# fuil_oil_counter.net
KiCad netlist of a schematic drawn in EAGLE
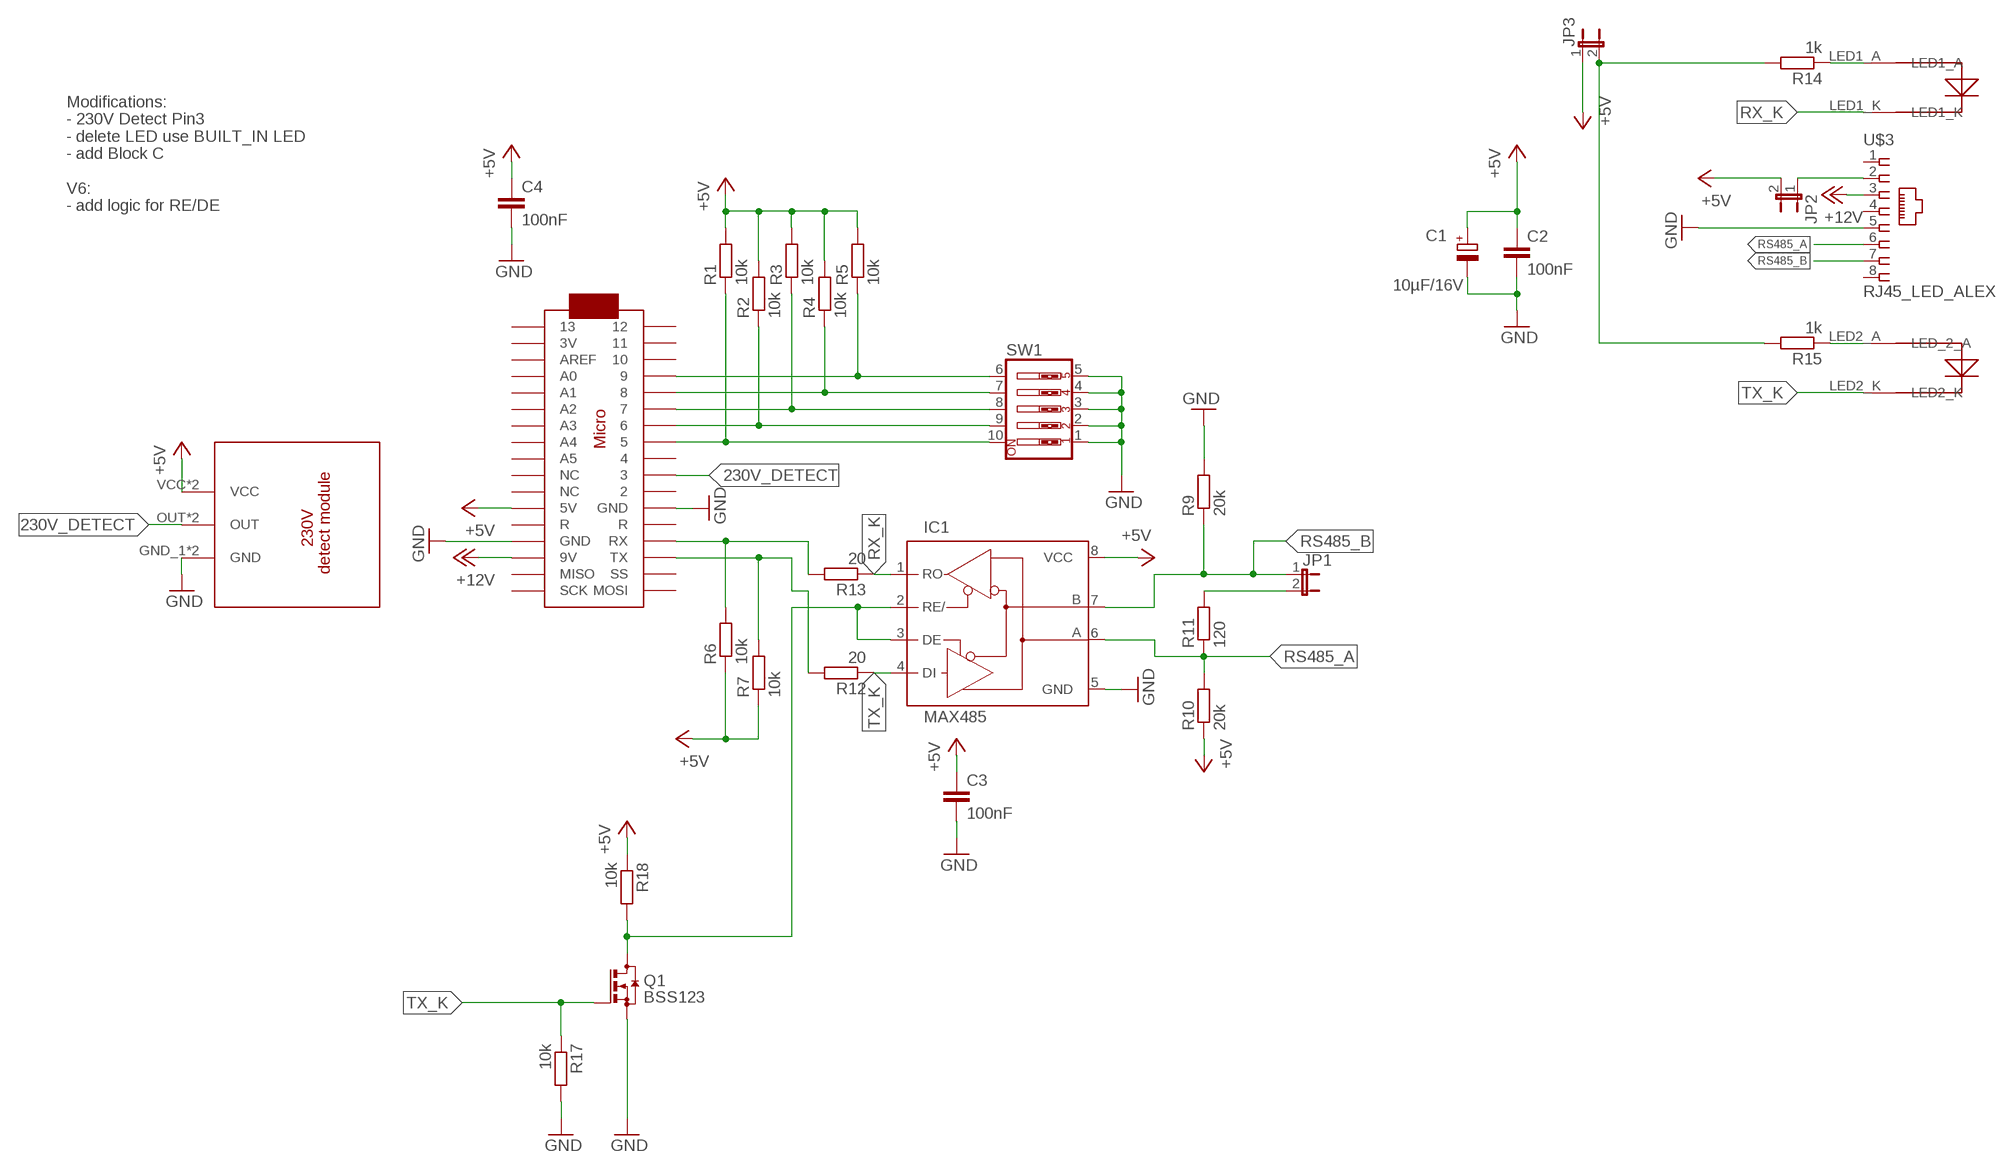
[diagram p0: schematic, sheet 1]

(export (version "E")
  (design (tool "Eeschema 10.0.6"))
  (components
    (comp (ref "C1")
      (value "10µF/16V")
      (footprint "eagle-import:SMC_C")
      (libsource (lib "eagle-import") (part "CPOL-EUSMCC"))
    )
    (comp (ref "C2")
      (value "100nF")
      (footprint "eagle-import:C0805")
      (libsource (lib "eagle-import") (part "C-EUC0805"))
    )
    (comp (ref "C3")
      (value "100nF")
      (footprint "eagle-import:C0805")
      (libsource (lib "eagle-import") (part "C-EUC0805"))
    )
    (comp (ref "C4")
      (value "100nF")
      (footprint "eagle-import:C0805")
      (libsource (lib "eagle-import") (part "C-EUC0805"))
    )
    (comp (ref "IC1")
      (value "MAX485")
      (footprint "eagle-import:SO08")
      (fields (field (name "MPN") "MAX3468ESA+T"))
      (libsource (lib "eagle-import") (part "MAX34SA68E"))
    )
    (comp (ref "JP1")
      (value "JP1E")
      (footprint "eagle-import:JP1")
      (libsource (lib "eagle-import") (part "JP1E"))
    )
    (comp (ref "JP2")
      (value "JP1E")
      (footprint "eagle-import:JP1")
      (libsource (lib "eagle-import") (part "JP1E"))
    )
    (comp (ref "JP3")
      (value "JP1E")
      (footprint "eagle-import:JP1")
      (libsource (lib "eagle-import") (part "JP1E"))
    )
    (comp (ref "Q1")
      (value "BSS123")
      (footprint "eagle-import:SOT23")
      (libsource (lib "eagle-import") (part "BSS123"))
    )
    (comp (ref "R1")
      (value "10k")
      (footprint "eagle-import:M0805")
      (libsource (lib "eagle-import") (part "R-EU_M0805"))
    )
    (comp (ref "R2")
      (value "10k")
      (footprint "eagle-import:M0805")
      (libsource (lib "eagle-import") (part "R-EU_M0805"))
    )
    (comp (ref "R3")
      (value "10k")
      (footprint "eagle-import:M0805")
      (libsource (lib "eagle-import") (part "R-EU_M0805"))
    )
    (comp (ref "R4")
      (value "10k")
      (footprint "eagle-import:M0805")
      (libsource (lib "eagle-import") (part "R-EU_M0805"))
    )
    (comp (ref "R5")
      (value "10k")
      (footprint "eagle-import:M0805")
      (libsource (lib "eagle-import") (part "R-EU_M0805"))
    )
    (comp (ref "R6")
      (value "10k")
      (footprint "eagle-import:M0805")
      (libsource (lib "eagle-import") (part "R-EU_M0805"))
    )
    (comp (ref "R7")
      (value "10k")
      (footprint "eagle-import:M0805")
      (libsource (lib "eagle-import") (part "R-EU_M0805"))
    )
    (comp (ref "R9")
      (value "20k")
      (footprint "eagle-import:M0805")
      (libsource (lib "eagle-import") (part "R-EU_M0805"))
    )
    (comp (ref "R10")
      (value "20k")
      (footprint "eagle-import:M0805")
      (libsource (lib "eagle-import") (part "R-EU_M0805"))
    )
    (comp (ref "R11")
      (value "120")
      (footprint "eagle-import:P0613_15")
      (libsource (lib "eagle-import") (part "R-EU_0613/15"))
    )
    (comp (ref "R12")
      (value "20")
      (footprint "eagle-import:M0805")
      (libsource (lib "eagle-import") (part "R-EU_M0805"))
    )
    (comp (ref "R13")
      (value "20")
      (footprint "eagle-import:M0805")
      (libsource (lib "eagle-import") (part "R-EU_M0805"))
    )
    (comp (ref "R14")
      (value "1k")
      (footprint "eagle-import:M0805")
      (libsource (lib "eagle-import") (part "R-EU_M0805"))
    )
    (comp (ref "R15")
      (value "1k")
      (footprint "eagle-import:M0805")
      (libsource (lib "eagle-import") (part "R-EU_M0805"))
    )
    (comp (ref "R17")
      (value "10k")
      (footprint "eagle-import:M0805")
      (libsource (lib "eagle-import") (part "resistor_R-EU_M0805"))
    )
    (comp (ref "R18")
      (value "10k")
      (footprint "eagle-import:M0805")
      (libsource (lib "eagle-import") (part "resistor_R-EU_M0805"))
    )
    (comp (ref "SW1")
      (value "SW_DIP-5")
      (footprint "eagle-import:EDG-05")
      (libsource (lib "eagle-import") (part "SW_DIP-5"))
    )
    (comp (ref "U$1")
      (value "ARDUINOMICRO")
      (footprint "eagle-import:ARDUINOMICRO")
      (libsource (lib "eagle-import") (part "ARDUINOMICRO"))
    )
    (comp (ref "U$2")
      (value "POWER_DETECT")
      (footprint "eagle-import:POWER_DETECT")
      (libsource (lib "eagle-import") (part "POWER_DETECT"))
    )
    (comp (ref "U$3")
      (value "RJ45_LED_ALEX")
      (footprint "eagle-import:RJ45-NO-SHIELD-WITH_LED")
      (libsource (lib "eagle-import") (part "RJ45_LED_ALEX"))
    )
  )
  (nets
    (net (code "1") (name "+5V") (class "Default")
      (node (ref "C1") (pin "+") (pinfunction "+_+") (pintype "passive"))
      (node (ref "C2") (pin "1") (pinfunction "1_1") (pintype "passive"))
      (node (ref "C3") (pin "1") (pinfunction "1_1") (pintype "passive"))
      (node (ref "C4") (pin "1") (pinfunction "1_1") (pintype "passive"))
      (node (ref "IC1") (pin "8") (pinfunction "VCC_8") (pintype "power_in"))
      (node (ref "JP2") (pin "2") (pinfunction "2_2") (pintype "passive"))
      (node (ref "JP3") (pin "1") (pinfunction "1_1") (pintype "passive"))
      (node (ref "R1") (pin "2") (pinfunction "2_2") (pintype "passive"))
      (node (ref "R10") (pin "1") (pinfunction "1_1") (pintype "passive"))
      (node (ref "R18") (pin "1") (pinfunction "1_1") (pintype "passive"))
      (node (ref "R2") (pin "2") (pinfunction "2_2") (pintype "passive"))
      (node (ref "R3") (pin "2") (pinfunction "2_2") (pintype "passive"))
      (node (ref "R4") (pin "2") (pinfunction "2_2") (pintype "passive"))
      (node (ref "R5") (pin "2") (pinfunction "2_2") (pintype "passive"))
      (node (ref "R6") (pin "1") (pinfunction "1_1") (pintype "passive"))
      (node (ref "R7") (pin "1") (pinfunction "1_1") (pintype "passive"))
      (node (ref "U$1") (pin "P$23") (pinfunction "5V_P$23") (pintype "bidirectional"))
      (node (ref "U$2") (pin "VCC") (pinfunction "VCC_VCC") (pintype "power_in"))
      (node (ref "U$2") (pin "VCC_2") (pinfunction "VCC_VCC_2") (pintype "power_in"))
    )
    (net (code "2") (name "+12V") (class "Default")
      (node (ref "U$1") (pin "P$20") (pinfunction "9V_P$20") (pintype "bidirectional"))
      (node (ref "U$3") (pin "3") (pinfunction "3_3") (pintype "passive"))
    )
    (net (code "3") (name "230V_DETECT") (class "Default")
      (node (ref "U$1") (pin "P$10") (pinfunction "3_P$10") (pintype "bidirectional"))
      (node (ref "U$2") (pin "OUT") (pinfunction "OUT_OUT") (pintype "output"))
      (node (ref "U$2") (pin "OUT_2") (pinfunction "OUT_OUT_2") (pintype "output"))
    )
    (net (code "4") (name "GND") (class "Default")
      (node (ref "C1") (pin "-") (pinfunction "-_-") (pintype "passive"))
      (node (ref "C2") (pin "2") (pinfunction "2_2") (pintype "passive"))
      (node (ref "C3") (pin "2") (pinfunction "2_2") (pintype "passive"))
      (node (ref "C4") (pin "2") (pinfunction "2_2") (pintype "passive"))
      (node (ref "IC1") (pin "5") (pinfunction "GND_5") (pintype "power_in"))
      (node (ref "Q1") (pin "2") (pinfunction "S_2") (pintype "passive"))
      (node (ref "R17") (pin "2") (pinfunction "2_2") (pintype "passive"))
      (node (ref "R9") (pin "2") (pinfunction "2_2") (pintype "passive"))
      (node (ref "SW1") (pin "1") (pinfunction "1_1") (pintype "passive"))
      (node (ref "SW1") (pin "2") (pinfunction "2_2") (pintype "passive"))
      (node (ref "SW1") (pin "3") (pinfunction "3_3") (pintype "passive"))
      (node (ref "SW1") (pin "4") (pinfunction "4_4") (pintype "passive"))
      (node (ref "SW1") (pin "5") (pinfunction "5_5") (pintype "passive"))
      (node (ref "U$1") (pin "P$12") (pinfunction "GND_P$12") (pintype "bidirectional"))
      (node (ref "U$1") (pin "P$21") (pinfunction "GND_P$21") (pintype "bidirectional"))
      (node (ref "U$2") (pin "GND_1") (pinfunction "GND_GND_1") (pintype "power_in"))
      (node (ref "U$2") (pin "GND_PIN") (pinfunction "GND_GND_PIN") (pintype "power_in"))
      (node (ref "U$3") (pin "5") (pinfunction "5_5") (pintype "passive"))
    )
    (net (code "5") (name "Net-(IC1-DE)") (class "Default")
      (node (ref "IC1") (pin "2") (pinfunction "RE/_2") (pintype "input"))
      (node (ref "IC1") (pin "3") (pinfunction "DE_3") (pintype "input"))
      (node (ref "Q1") (pin "3") (pinfunction "D_3") (pintype "passive"))
      (node (ref "R18") (pin "2") (pinfunction "2_2") (pintype "passive"))
    )
    (net (code "6") (name "Net-(JP1-Pad2)") (class "Default")
      (node (ref "JP1") (pin "2") (pinfunction "2_2") (pintype "passive"))
      (node (ref "R11") (pin "2") (pinfunction "2_2") (pintype "passive"))
    )
    (net (code "7") (name "Net-(JP2-Pad1)") (class "Default")
      (node (ref "JP2") (pin "1") (pinfunction "1_1") (pintype "passive"))
      (node (ref "U$3") (pin "2") (pinfunction "2_2") (pintype "passive"))
    )
    (net (code "8") (name "Net-(JP3-Pad2)") (class "Default")
      (node (ref "JP3") (pin "2") (pinfunction "2_2") (pintype "passive"))
      (node (ref "R14") (pin "2") (pinfunction "2_2") (pintype "passive"))
      (node (ref "R15") (pin "2") (pinfunction "2_2") (pintype "passive"))
    )
    (net (code "9") (name "Net-(R14-Pad1)") (class "Default")
      (node (ref "R14") (pin "1") (pinfunction "1_1") (pintype "passive"))
      (node (ref "U$3") (pin "LED1_A") (pinfunction "LED1_A_LED1_A") (pintype "bidirectional"))
    )
    (net (code "10") (name "Net-(U$1-5)") (class "Default")
      (node (ref "R1") (pin "1") (pinfunction "1_1") (pintype "passive"))
      (node (ref "SW1") (pin "10") (pinfunction "10_10") (pintype "passive"))
      (node (ref "U$1") (pin "P$8") (pinfunction "5_P$8") (pintype "bidirectional"))
    )
    (net (code "11") (name "Net-(U$1-6)") (class "Default")
      (node (ref "R2") (pin "1") (pinfunction "1_1") (pintype "passive"))
      (node (ref "SW1") (pin "9") (pinfunction "9_9") (pintype "passive"))
      (node (ref "U$1") (pin "P$7") (pinfunction "6_P$7") (pintype "bidirectional"))
    )
    (net (code "12") (name "Net-(U$1-7)") (class "Default")
      (node (ref "R3") (pin "1") (pinfunction "1_1") (pintype "passive"))
      (node (ref "SW1") (pin "8") (pinfunction "8_8") (pintype "passive"))
      (node (ref "U$1") (pin "P$6") (pinfunction "7_P$6") (pintype "bidirectional"))
    )
    (net (code "13") (name "Net-(U$1-8)") (class "Default")
      (node (ref "R4") (pin "1") (pinfunction "1_1") (pintype "passive"))
      (node (ref "SW1") (pin "7") (pinfunction "7_7") (pintype "passive"))
      (node (ref "U$1") (pin "P$5") (pinfunction "8_P$5") (pintype "bidirectional"))
    )
    (net (code "14") (name "Net-(U$1-9)") (class "Default")
      (node (ref "R5") (pin "1") (pinfunction "1_1") (pintype "passive"))
      (node (ref "SW1") (pin "6") (pinfunction "6_6") (pintype "passive"))
      (node (ref "U$1") (pin "P$4") (pinfunction "9_P$4") (pintype "bidirectional"))
    )
    (net (code "15") (name "Net-(U$1-RX)") (class "Default")
      (node (ref "R13") (pin "2") (pinfunction "2_2") (pintype "passive"))
      (node (ref "R6") (pin "2") (pinfunction "2_2") (pintype "passive"))
      (node (ref "U$1") (pin "P$14") (pinfunction "RX_P$14") (pintype "bidirectional"))
    )
    (net (code "16") (name "Net-(U$1-TX)") (class "Default")
      (node (ref "R12") (pin "2") (pinfunction "2_2") (pintype "passive"))
      (node (ref "R7") (pin "2") (pinfunction "2_2") (pintype "passive"))
      (node (ref "U$1") (pin "P$15") (pinfunction "TX_P$15") (pintype "bidirectional"))
    )
    (net (code "17") (name "Net-(U$3-LED_2_A)") (class "Default")
      (node (ref "R15") (pin "1") (pinfunction "1_1") (pintype "passive"))
      (node (ref "U$3") (pin "LED2_A") (pinfunction "LED_2_A_LED2_A") (pintype "bidirectional"))
    )
    (net (code "18") (name "RS485_A") (class "Default")
      (node (ref "IC1") (pin "6") (pinfunction "A_6") (pintype "passive"))
      (node (ref "R10") (pin "2") (pinfunction "2_2") (pintype "passive"))
      (node (ref "R11") (pin "1") (pinfunction "1_1") (pintype "passive"))
      (node (ref "U$3") (pin "6") (pinfunction "6_6") (pintype "passive"))
    )
    (net (code "19") (name "RS485_B") (class "Default")
      (node (ref "IC1") (pin "7") (pinfunction "B_7") (pintype "passive"))
      (node (ref "JP1") (pin "1") (pinfunction "1_1") (pintype "passive"))
      (node (ref "R9") (pin "1") (pinfunction "1_1") (pintype "passive"))
      (node (ref "U$3") (pin "7") (pinfunction "7_7") (pintype "passive"))
    )
    (net (code "20") (name "RX_K") (class "Default")
      (node (ref "IC1") (pin "1") (pinfunction "RO_1") (pintype "output"))
      (node (ref "R13") (pin "1") (pinfunction "1_1") (pintype "passive"))
      (node (ref "U$3") (pin "LED1_K") (pinfunction "LED1_K_LED1_K") (pintype "bidirectional"))
    )
    (net (code "21") (name "TX_K") (class "Default")
      (node (ref "IC1") (pin "4") (pinfunction "DI_4") (pintype "input"))
      (node (ref "Q1") (pin "1") (pinfunction "G_1") (pintype "passive"))
      (node (ref "R12") (pin "1") (pinfunction "1_1") (pintype "passive"))
      (node (ref "R17") (pin "1") (pinfunction "1_1") (pintype "passive"))
      (node (ref "U$3") (pin "LED2_K") (pinfunction "LED2_K_LED2_K") (pintype "bidirectional"))
    )
    (net (code "22") (name "unconnected-(U$1-2-PadP$11)") (class "Default")
      (node (ref "U$1") (pin "P$11") (pinfunction "2_P$11") (pintype "bidirectional"))
    )
    (net (code "23") (name "unconnected-(U$1-3V-PadP$33)") (class "Default")
      (node (ref "U$1") (pin "P$33") (pinfunction "3V_P$33") (pintype "bidirectional"))
    )
    (net (code "24") (name "unconnected-(U$1-4-PadP$9)") (class "Default")
      (node (ref "U$1") (pin "P$9") (pinfunction "4_P$9") (pintype "bidirectional"))
    )
    (net (code "25") (name "unconnected-(U$1-10-PadP$3)") (class "Default")
      (node (ref "U$1") (pin "P$3") (pinfunction "10_P$3") (pintype "bidirectional"))
    )
    (net (code "26") (name "unconnected-(U$1-11-PadP$2)") (class "Default")
      (node (ref "U$1") (pin "P$2") (pinfunction "11_P$2") (pintype "bidirectional"))
    )
    (net (code "27") (name "unconnected-(U$1-12-PadP$1)") (class "Default")
      (node (ref "U$1") (pin "P$1") (pinfunction "12_P$1") (pintype "bidirectional"))
    )
    (net (code "28") (name "unconnected-(U$1-13-PadP$34)") (class "Default")
      (node (ref "U$1") (pin "P$34") (pinfunction "13_P$34") (pintype "bidirectional"))
    )
    (net (code "29") (name "unconnected-(U$1-A0-PadP$31)") (class "Default")
      (node (ref "U$1") (pin "P$31") (pinfunction "A0_P$31") (pintype "bidirectional"))
    )
    (net (code "30") (name "unconnected-(U$1-A1-PadP$30)") (class "Default")
      (node (ref "U$1") (pin "P$30") (pinfunction "A1_P$30") (pintype "bidirectional"))
    )
    (net (code "31") (name "unconnected-(U$1-A2-PadP$29)") (class "Default")
      (node (ref "U$1") (pin "P$29") (pinfunction "A2_P$29") (pintype "bidirectional"))
    )
    (net (code "32") (name "unconnected-(U$1-A3-PadP$28)") (class "Default")
      (node (ref "U$1") (pin "P$28") (pinfunction "A3_P$28") (pintype "bidirectional"))
    )
    (net (code "33") (name "unconnected-(U$1-A4-PadP$27)") (class "Default")
      (node (ref "U$1") (pin "P$27") (pinfunction "A4_P$27") (pintype "bidirectional"))
    )
    (net (code "34") (name "unconnected-(U$1-A5-PadP$26)") (class "Default")
      (node (ref "U$1") (pin "P$26") (pinfunction "A5_P$26") (pintype "bidirectional"))
    )
    (net (code "35") (name "unconnected-(U$1-AREF-PadP$32)") (class "Default")
      (node (ref "U$1") (pin "P$32") (pinfunction "AREF_P$32") (pintype "bidirectional"))
    )
    (net (code "36") (name "unconnected-(U$1-MISO-PadP$19)") (class "Default")
      (node (ref "U$1") (pin "P$19") (pinfunction "MISO_P$19") (pintype "bidirectional"))
    )
    (net (code "37") (name "unconnected-(U$1-MOSI-PadP$17)") (class "Default")
      (node (ref "U$1") (pin "P$17") (pinfunction "MOSI_P$17") (pintype "bidirectional"))
    )
    (net (code "38") (name "unconnected-(U$1-NC-PadP$24)") (class "Default")
      (node (ref "U$1") (pin "P$24") (pinfunction "NC_P$24") (pintype "bidirectional"))
    )
    (net (code "39") (name "unconnected-(U$1-NC-PadP$25)") (class "Default")
      (node (ref "U$1") (pin "P$25") (pinfunction "NC_P$25") (pintype "bidirectional"))
    )
    (net (code "40") (name "unconnected-(U$1-R-PadP$13)") (class "Default")
      (node (ref "U$1") (pin "P$13") (pinfunction "R_P$13") (pintype "bidirectional"))
    )
    (net (code "41") (name "unconnected-(U$1-R-PadP$22)") (class "Default")
      (node (ref "U$1") (pin "P$22") (pinfunction "R_P$22") (pintype "bidirectional"))
    )
    (net (code "42") (name "unconnected-(U$1-SCK-PadP$18)") (class "Default")
      (node (ref "U$1") (pin "P$18") (pinfunction "SCK_P$18") (pintype "bidirectional"))
    )
    (net (code "43") (name "unconnected-(U$1-SS-PadP$16)") (class "Default")
      (node (ref "U$1") (pin "P$16") (pinfunction "SS_P$16") (pintype "bidirectional"))
    )
    (net (code "44") (name "unconnected-(U$3-Pad1)") (class "Default")
      (node (ref "U$3") (pin "1") (pinfunction "1_1") (pintype "passive"))
    )
    (net (code "45") (name "unconnected-(U$3-Pad4)") (class "Default")
      (node (ref "U$3") (pin "4") (pinfunction "4_4") (pintype "passive"))
    )
    (net (code "46") (name "unconnected-(U$3-Pad8)") (class "Default")
      (node (ref "U$3") (pin "8") (pinfunction "8_8") (pintype "passive"))
    )
  )
)
